# Unvrsl_INA125P_V1.net
KiCad netlist of a schematic drawn in EAGLE
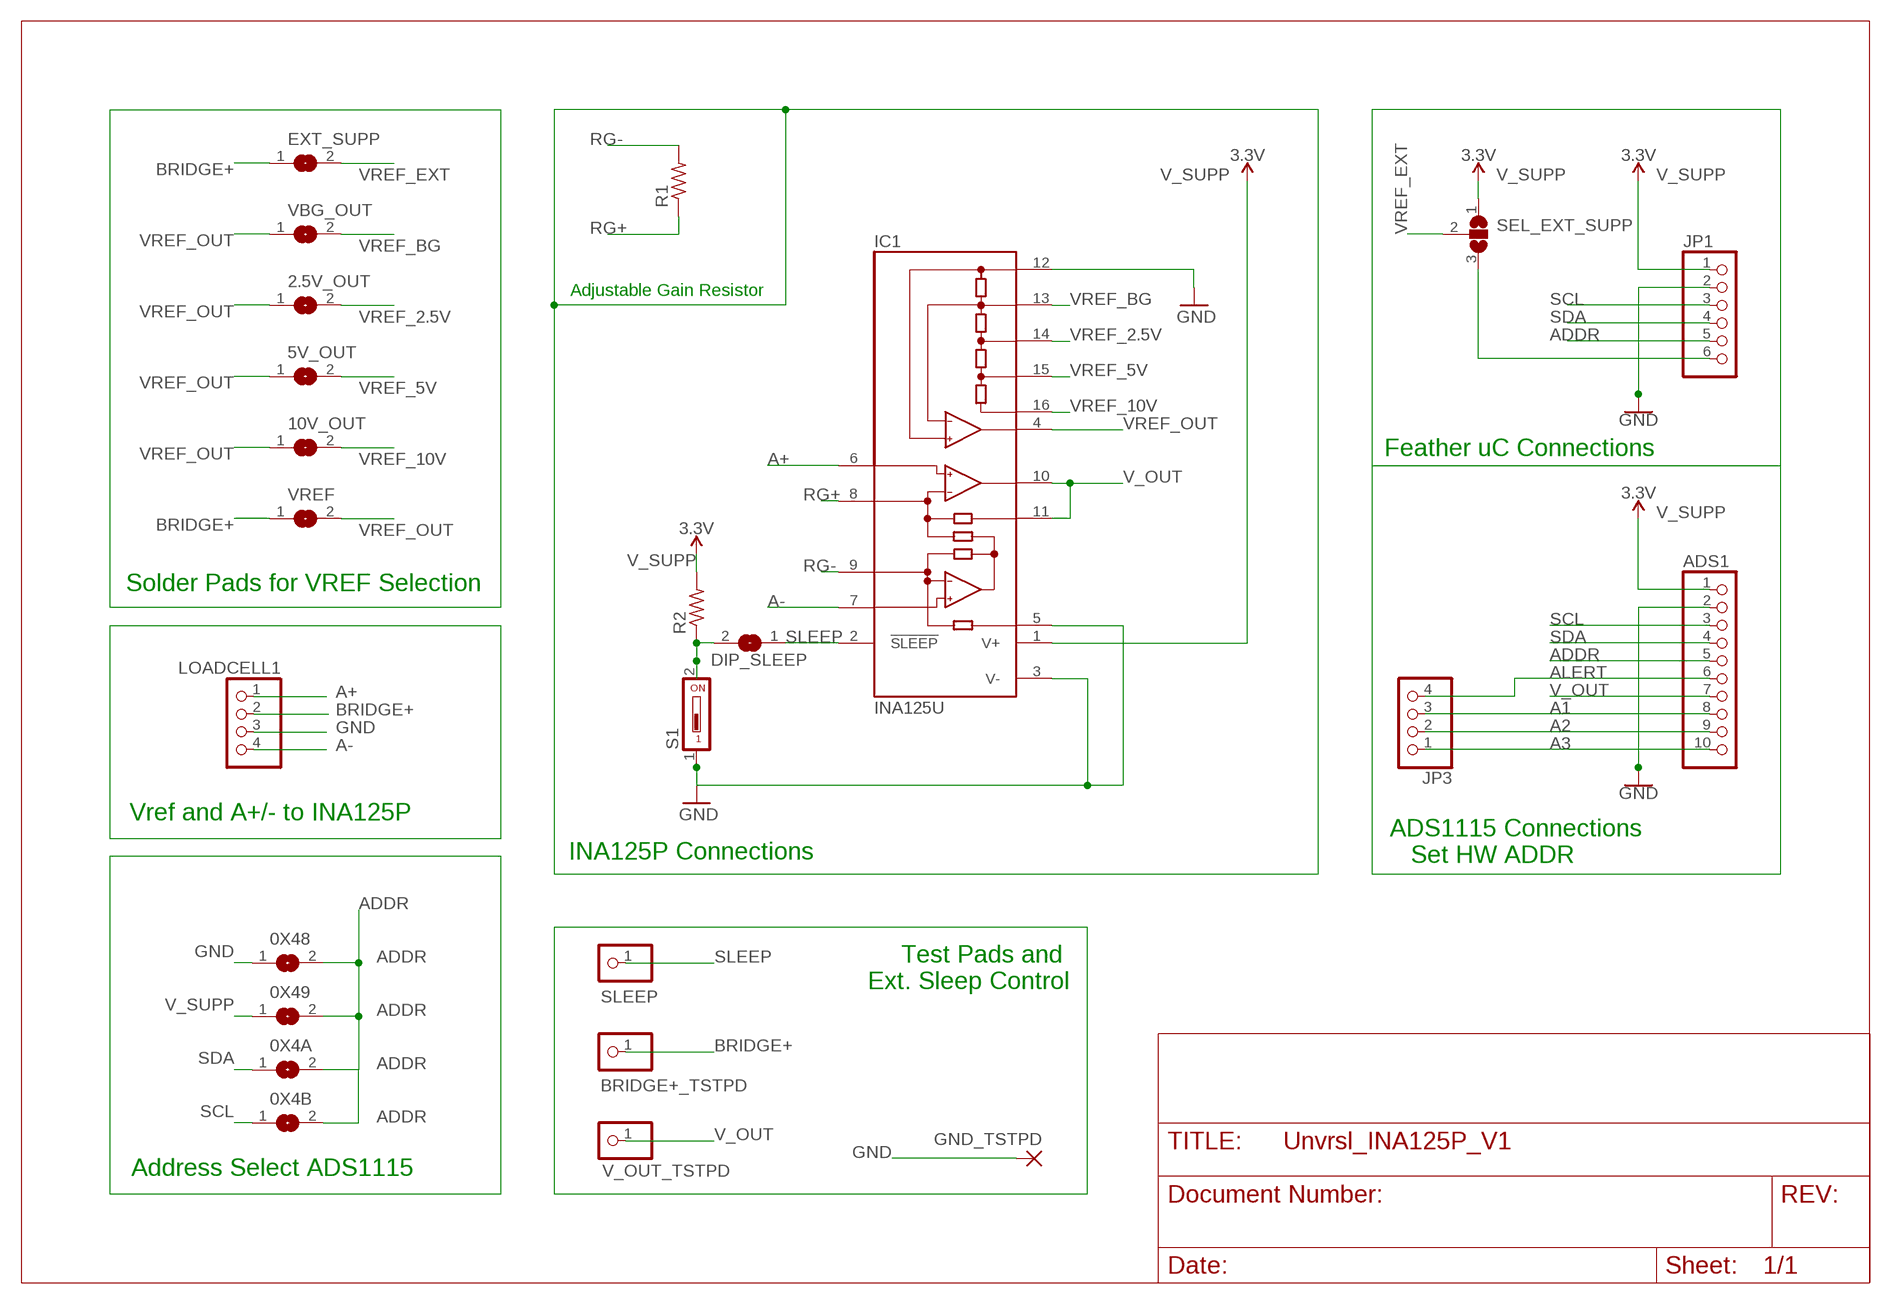
[diagram p0: schematic, sheet 1]

(export (version "E")
  (design (tool "Eeschema 10.0.6"))
  (components
    (comp (ref "0X4A")
      (value "SJ")
      (footprint "eagle-import:SJ")
      (libsource (lib "eagle-import") (part "SJ"))
    )
    (comp (ref "0X4B")
      (value "SJ")
      (footprint "eagle-import:SJ")
      (libsource (lib "eagle-import") (part "SJ"))
    )
    (comp (ref "0X48")
      (value "SJ")
      (footprint "eagle-import:SJ")
      (libsource (lib "eagle-import") (part "SJ"))
    )
    (comp (ref "0X49")
      (value "SJ")
      (footprint "eagle-import:SJ")
      (libsource (lib "eagle-import") (part "SJ"))
    )
    (comp (ref "2.5V_OUT")
      (value "SJ")
      (footprint "eagle-import:SJ")
      (libsource (lib "eagle-import") (part "SJ"))
    )
    (comp (ref "5V_OUT")
      (value "SJ")
      (footprint "eagle-import:SJ")
      (libsource (lib "eagle-import") (part "SJ"))
    )
    (comp (ref "10V_OUT")
      (value "SJ")
      (footprint "eagle-import:SJ")
      (libsource (lib "eagle-import") (part "SJ"))
    )
    (comp (ref "ADS1")
      (value "PINHD-1X10")
      (footprint "eagle-import:1X10")
      (libsource (lib "eagle-import") (part "PINHD-1X10"))
    )
    (comp (ref "BRIDGE+_TSTPD")
      (value "PINHD-1X1")
      (footprint "eagle-import:1X01")
      (libsource (lib "eagle-import") (part "PINHD-1X1"))
    )
    (comp (ref "DIP_SLEEP")
      (value "SJ")
      (footprint "eagle-import:SJ")
      (libsource (lib "eagle-import") (part "SJ"))
    )
    (comp (ref "EXT_SUPP")
      (value "SJ")
      (footprint "eagle-import:SJ")
      (libsource (lib "eagle-import") (part "SJ"))
    )
    (comp (ref "GND_TSTPD")
      (value "WIREPADSMD2,54-5,08")
      (footprint "eagle-import:SMD2,54-5,08")
      (libsource (lib "eagle-import") (part "WIREPADSMD2,54-5,08"))
    )
    (comp (ref "IC1")
      (value "INA125U")
      (footprint "eagle-import:SO16-1")
      (fields (field (name "MF") "TEXAS INSTRUMENT CONNECTORS"))
      (libsource (lib "eagle-import") (part "INA125U"))
    )
    (comp (ref "JP1")
      (value "PINHD-1X6")
      (footprint "eagle-import:1X06")
      (libsource (lib "eagle-import") (part "PINHD-1X6"))
    )
    (comp (ref "JP3")
      (value "PINHD-1X4")
      (footprint "eagle-import:1X04")
      (libsource (lib "eagle-import") (part "PINHD-1X4"))
    )
    (comp (ref "LOADCELL1")
      (value "PINHD-1X4")
      (footprint "eagle-import:1X04")
      (libsource (lib "eagle-import") (part "PINHD-1X4"))
    )
    (comp (ref "R1")
      (value "R-US_R0603")
      (footprint "eagle-import:R0603")
      (libsource (lib "eagle-import") (part "R-US_R0603"))
    )
    (comp (ref "R2")
      (value "R-US_R1206")
      (footprint "eagle-import:R1206")
      (libsource (lib "eagle-import") (part "R-US_R1206"))
    )
    (comp (ref "S1")
      (value "DS01")
      (footprint "eagle-import:DS-01")
      (libsource (lib "eagle-import") (part "DS01"))
    )
    (comp (ref "SEL_EXT_SUPP")
      (value "SJ2WW")
      (footprint "eagle-import:SJ_2W")
      (libsource (lib "eagle-import") (part "SJ2WW"))
    )
    (comp (ref "SLEEP")
      (value "PINHD-1X1")
      (footprint "eagle-import:1X01")
      (libsource (lib "eagle-import") (part "PINHD-1X1"))
    )
    (comp (ref "VBG_OUT")
      (value "SJ")
      (footprint "eagle-import:SJ")
      (libsource (lib "eagle-import") (part "SJ"))
    )
    (comp (ref "VREF")
      (value "SJ")
      (footprint "eagle-import:SJ")
      (libsource (lib "eagle-import") (part "SJ"))
    )
    (comp (ref "V_OUT_TSTPD")
      (value "PINHD-1X1")
      (footprint "eagle-import:1X01")
      (libsource (lib "eagle-import") (part "PINHD-1X1"))
    )
  )
  (nets
    (net (code "1") (name "/A+") (class "Default")
      (node (ref "IC1") (pin "6") (pinfunction "+IN_6") (pintype "input"))
      (node (ref "LOADCELL1") (pin "1") (pinfunction "1_1") (pintype "passive"))
    )
    (net (code "2") (name "/A-") (class "Default")
      (node (ref "IC1") (pin "7") (pinfunction "-IN_7") (pintype "input"))
      (node (ref "LOADCELL1") (pin "4") (pinfunction "4_4") (pintype "passive"))
    )
    (net (code "3") (name "/A1") (class "Default")
      (node (ref "ADS1") (pin "8") (pinfunction "8_8") (pintype "passive"))
      (node (ref "JP3") (pin "3") (pinfunction "3_3") (pintype "passive"))
    )
    (net (code "4") (name "/A2") (class "Default")
      (node (ref "ADS1") (pin "9") (pinfunction "9_9") (pintype "passive"))
      (node (ref "JP3") (pin "2") (pinfunction "2_2") (pintype "passive"))
    )
    (net (code "5") (name "/A3") (class "Default")
      (node (ref "ADS1") (pin "10") (pinfunction "10_10") (pintype "passive"))
      (node (ref "JP3") (pin "1") (pinfunction "1_1") (pintype "passive"))
    )
    (net (code "6") (name "/ADDR") (class "Default")
      (node (ref "0X48") (pin "2") (pinfunction "2_2") (pintype "passive"))
      (node (ref "0X49") (pin "2") (pinfunction "2_2") (pintype "passive"))
      (node (ref "0X4A") (pin "2") (pinfunction "2_2") (pintype "passive"))
      (node (ref "0X4B") (pin "2") (pinfunction "2_2") (pintype "passive"))
      (node (ref "ADS1") (pin "5") (pinfunction "5_5") (pintype "passive"))
      (node (ref "JP1") (pin "5") (pinfunction "5_5") (pintype "passive"))
    )
    (net (code "7") (name "/ALERT") (class "Default")
      (node (ref "ADS1") (pin "6") (pinfunction "6_6") (pintype "passive"))
      (node (ref "JP3") (pin "4") (pinfunction "4_4") (pintype "passive"))
    )
    (net (code "8") (name "/BRIDGE+") (class "Default")
      (node (ref "BRIDGE+_TSTPD") (pin "1") (pinfunction "1_1") (pintype "passive"))
      (node (ref "EXT_SUPP") (pin "1") (pinfunction "1_1") (pintype "passive"))
      (node (ref "LOADCELL1") (pin "2") (pinfunction "2_2") (pintype "passive"))
      (node (ref "VREF") (pin "1") (pinfunction "1_1") (pintype "passive"))
    )
    (net (code "9") (name "/RG+") (class "Default")
      (node (ref "IC1") (pin "8") (pinfunction "RG_8") (pintype "passive"))
      (node (ref "R1") (pin "1") (pinfunction "1_1") (pintype "passive"))
    )
    (net (code "10") (name "/RG-") (class "Default")
      (node (ref "IC1") (pin "9") (pinfunction "RG_9") (pintype "passive"))
      (node (ref "R1") (pin "2") (pinfunction "2_2") (pintype "passive"))
    )
    (net (code "11") (name "/SCL") (class "Default")
      (node (ref "0X4B") (pin "1") (pinfunction "1_1") (pintype "passive"))
      (node (ref "ADS1") (pin "3") (pinfunction "3_3") (pintype "passive"))
      (node (ref "JP1") (pin "3") (pinfunction "3_3") (pintype "passive"))
    )
    (net (code "12") (name "/SDA") (class "Default")
      (node (ref "0X4A") (pin "1") (pinfunction "1_1") (pintype "passive"))
      (node (ref "ADS1") (pin "4") (pinfunction "4_4") (pintype "passive"))
      (node (ref "JP1") (pin "4") (pinfunction "4_4") (pintype "passive"))
    )
    (net (code "13") (name "/SLEEP") (class "Default")
      (node (ref "DIP_SLEEP") (pin "1") (pinfunction "1_1") (pintype "passive"))
      (node (ref "IC1") (pin "2") (pinfunction "~{SLEEP}_2") (pintype "input"))
      (node (ref "SLEEP") (pin "1") (pinfunction "1_1") (pintype "passive"))
    )
    (net (code "14") (name "/VREF_2.5V") (class "Default")
      (node (ref "2.5V_OUT") (pin "2") (pinfunction "2_2") (pintype "passive"))
      (node (ref "IC1") (pin "14") (pinfunction "REF2.5_14") (pintype "output"))
    )
    (net (code "15") (name "/VREF_5V") (class "Default")
      (node (ref "5V_OUT") (pin "2") (pinfunction "2_2") (pintype "passive"))
      (node (ref "IC1") (pin "15") (pinfunction "REF5_15") (pintype "output"))
    )
    (net (code "16") (name "/VREF_10V") (class "Default")
      (node (ref "10V_OUT") (pin "2") (pinfunction "2_2") (pintype "passive"))
      (node (ref "IC1") (pin "16") (pinfunction "REF10_16") (pintype "output"))
    )
    (net (code "17") (name "/VREF_BG") (class "Default")
      (node (ref "IC1") (pin "13") (pinfunction "REFBG_13") (pintype "output"))
      (node (ref "VBG_OUT") (pin "2") (pinfunction "2_2") (pintype "passive"))
    )
    (net (code "18") (name "/VREF_EXT") (class "Default")
      (node (ref "EXT_SUPP") (pin "2") (pinfunction "2_2") (pintype "passive"))
      (node (ref "SEL_EXT_SUPP") (pin "2") (pinfunction "2_2") (pintype "passive"))
    )
    (net (code "19") (name "/VREF_OUT") (class "Default")
      (node (ref "10V_OUT") (pin "1") (pinfunction "1_1") (pintype "passive"))
      (node (ref "2.5V_OUT") (pin "1") (pinfunction "1_1") (pintype "passive"))
      (node (ref "5V_OUT") (pin "1") (pinfunction "1_1") (pintype "passive"))
      (node (ref "IC1") (pin "4") (pinfunction "REFOUT_4") (pintype "output"))
      (node (ref "VBG_OUT") (pin "1") (pinfunction "1_1") (pintype "passive"))
      (node (ref "VREF") (pin "2") (pinfunction "2_2") (pintype "passive"))
    )
    (net (code "20") (name "/V_OUT") (class "Default")
      (node (ref "ADS1") (pin "7") (pinfunction "7_7") (pintype "passive"))
      (node (ref "IC1") (pin "10") (pinfunction "OUT_10") (pintype "output"))
      (node (ref "IC1") (pin "11") (pinfunction "SENSE_11") (pintype "passive"))
      (node (ref "V_OUT_TSTPD") (pin "1") (pinfunction "1_1") (pintype "passive"))
    )
    (net (code "21") (name "3.3V") (class "Default")
      (node (ref "0X49") (pin "1") (pinfunction "1_1") (pintype "passive"))
      (node (ref "ADS1") (pin "1") (pinfunction "1_1") (pintype "passive"))
      (node (ref "IC1") (pin "1") (pinfunction "V+_1") (pintype "power_in"))
      (node (ref "JP1") (pin "1") (pinfunction "1_1") (pintype "passive"))
      (node (ref "R2") (pin "2") (pinfunction "2_2") (pintype "passive"))
      (node (ref "SEL_EXT_SUPP") (pin "1") (pinfunction "1_1") (pintype "passive"))
    )
    (net (code "22") (name "GND") (class "Default")
      (node (ref "0X48") (pin "1") (pinfunction "1_1") (pintype "passive"))
      (node (ref "ADS1") (pin "2") (pinfunction "2_2") (pintype "passive"))
      (node (ref "GND_TSTPD") (pin "1") (pinfunction "P_1") (pintype "passive"))
      (node (ref "IC1") (pin "12") (pinfunction "REFCOM_12") (pintype "passive"))
      (node (ref "IC1") (pin "3") (pinfunction "V-_3") (pintype "power_in"))
      (node (ref "IC1") (pin "5") (pinfunction "REF_5") (pintype "passive"))
      (node (ref "JP1") (pin "2") (pinfunction "2_2") (pintype "passive"))
      (node (ref "LOADCELL1") (pin "3") (pinfunction "3_3") (pintype "passive"))
      (node (ref "S1") (pin "1") (pinfunction "1_1") (pintype "passive"))
    )
    (net (code "23") (name "Net-(DIP_SLEEP-Pad2)") (class "Default")
      (node (ref "DIP_SLEEP") (pin "2") (pinfunction "2_2") (pintype "passive"))
      (node (ref "R2") (pin "1") (pinfunction "1_1") (pintype "passive"))
      (node (ref "S1") (pin "2") (pinfunction "2_2") (pintype "passive"))
    )
    (net (code "24") (name "Net-(JP1-Pad6)") (class "Default")
      (node (ref "JP1") (pin "6") (pinfunction "6_6") (pintype "passive"))
      (node (ref "SEL_EXT_SUPP") (pin "3") (pinfunction "3_3") (pintype "passive"))
    )
  )
)
